# board.net
KiCad netlist of a schematic drawn in EAGLE
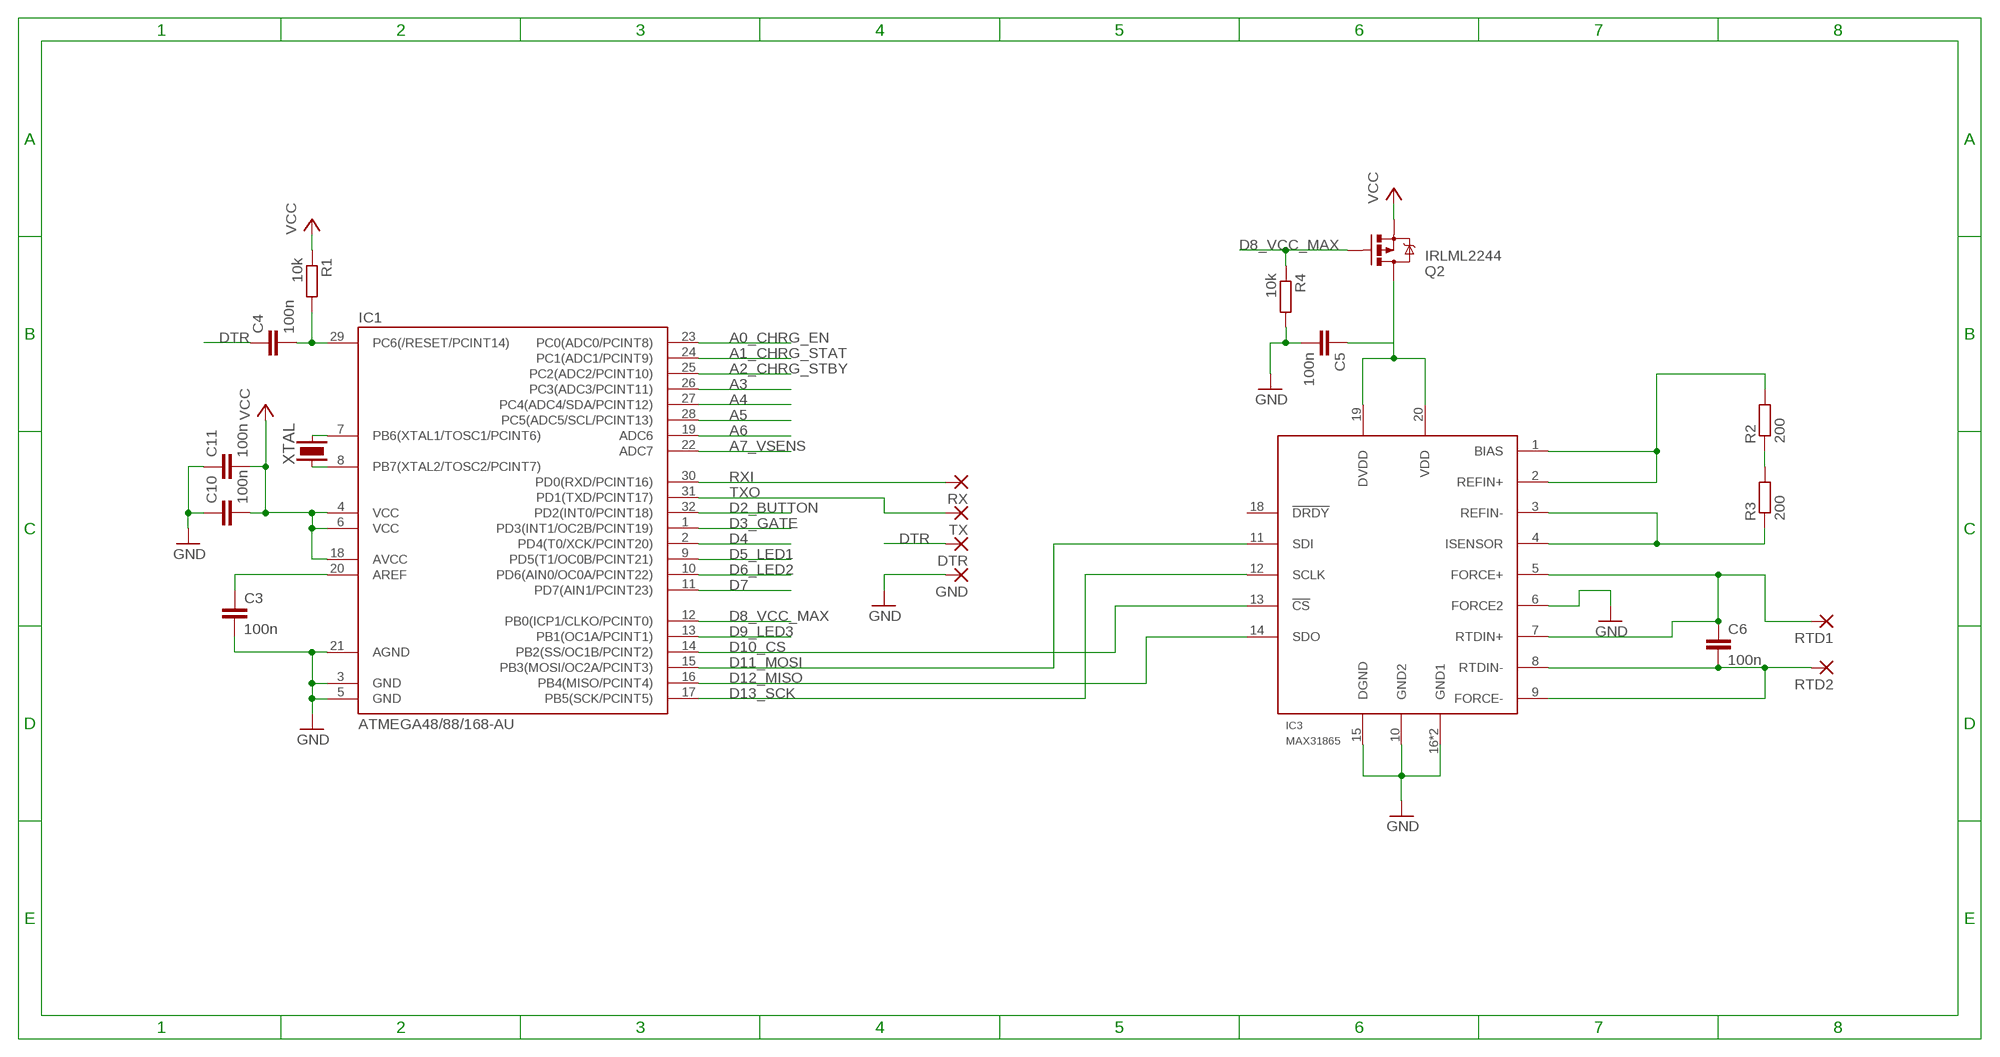
[diagram p0: schematic, sheet 1]
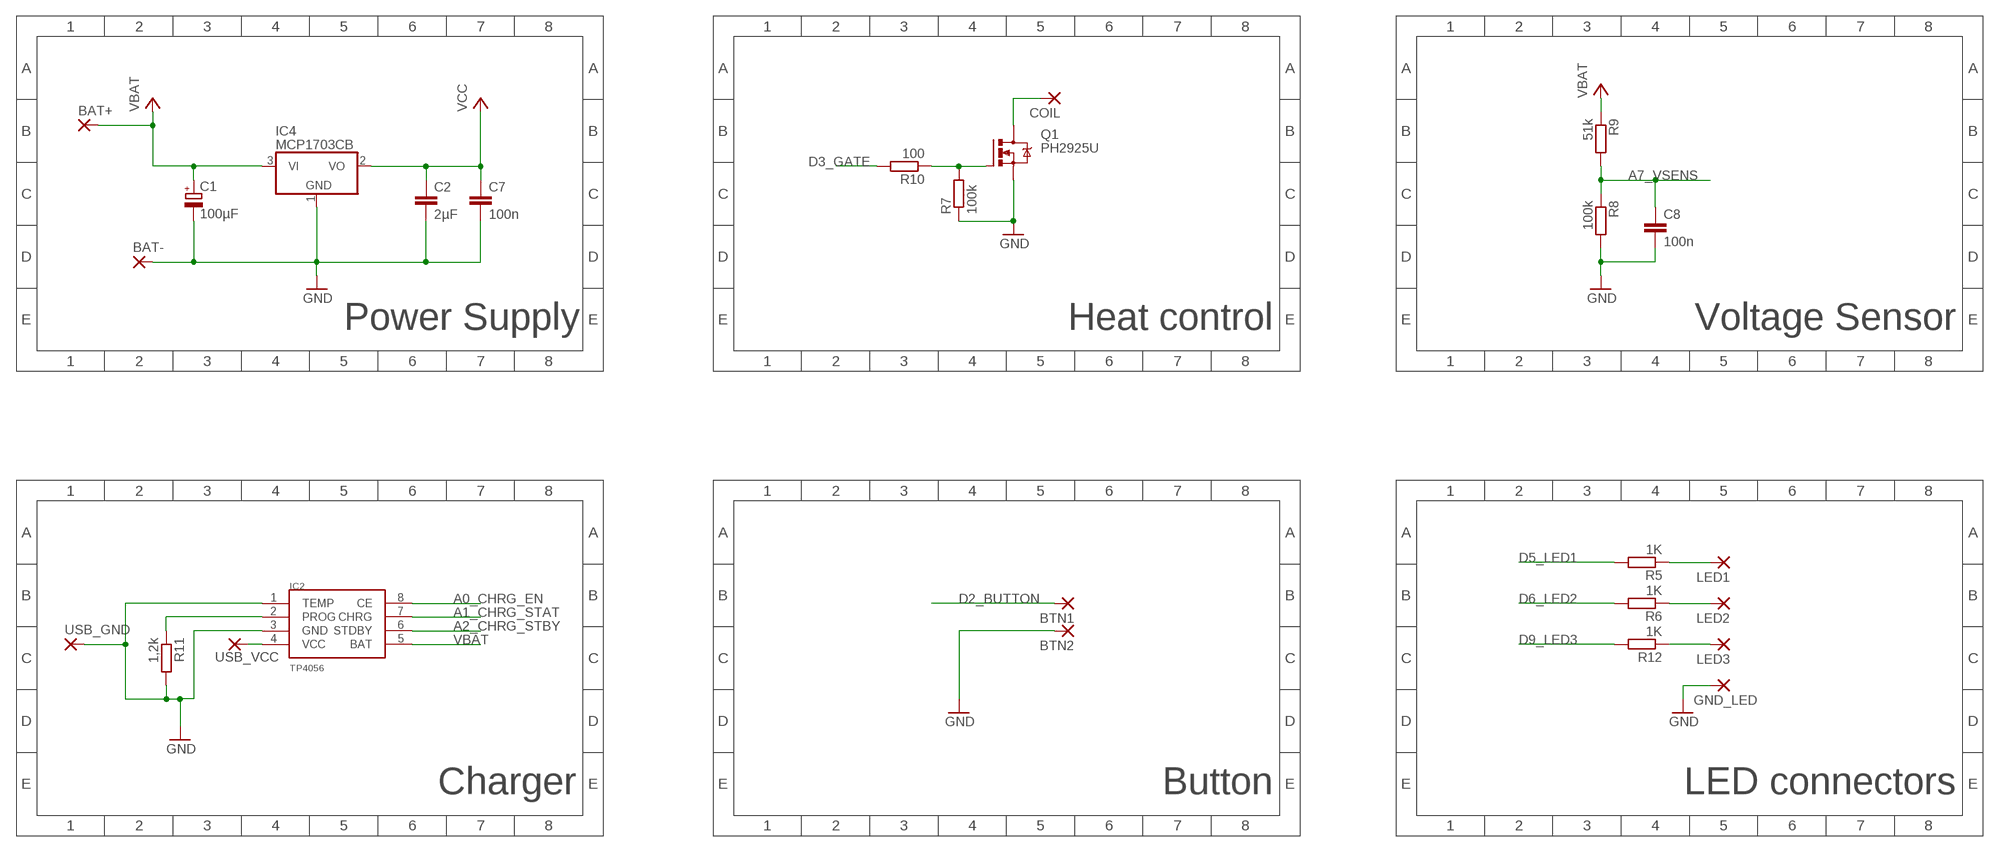
[diagram p1: schematic, sheet 2]

(export (version "E")
  (design (tool "Eeschema 10.0.6"))
  (components
    (comp (ref "BAT+")
      (value "SMD2")
      (footprint "eagle-import:SMD1,27-2,54")
      (libsource (lib "eagle-import") (part "SMD2"))
    )
    (comp (ref "BAT-")
      (value "WIREPAD4,16O1,6")
      (footprint "eagle-import:4,16O1,6")
      (libsource (lib "eagle-import") (part "WIREPAD4,16O1,6"))
    )
    (comp (ref "BTN1")
      (value "SMD2")
      (footprint "eagle-import:SMD1,27-2,54")
      (libsource (lib "eagle-import") (part "SMD2"))
    )
    (comp (ref "BTN2")
      (value "SMD2")
      (footprint "eagle-import:SMD1,27-2,54")
      (libsource (lib "eagle-import") (part "SMD2"))
    )
    (comp (ref "C1")
      (value "100µF")
      (footprint "eagle-import:CT7343")
      (libsource (lib "eagle-import") (part "CPOL-EUCT7343"))
    )
    (comp (ref "C2")
      (value "2µF")
      (footprint "eagle-import:C1206")
      (libsource (lib "eagle-import") (part "C-EUC1206"))
    )
    (comp (ref "C7")
      (value "100n")
      (footprint "eagle-import:C0603")
      (libsource (lib "eagle-import") (part "C-EUC0603"))
    )
    (comp (ref "C8")
      (value "100n")
      (footprint "eagle-import:C0603")
      (libsource (lib "eagle-import") (part "C-EUC0603"))
    )
    (comp (ref "COIL")
      (value "WIREPAD4,16O1,6")
      (footprint "eagle-import:4,16O1,6")
      (libsource (lib "eagle-import") (part "WIREPAD4,16O1,6"))
    )
    (comp (ref "GND_LED")
      (value "SMD2")
      (footprint "eagle-import:SMD1,27-2,54")
      (libsource (lib "eagle-import") (part "SMD2"))
    )
    (comp (ref "IC2")
      (value "TP4056")
      (footprint "eagle-import:SOP-8")
      (libsource (lib "eagle-import") (part "TP4056"))
    )
    (comp (ref "IC4")
      (value "MCP1703CB")
      (footprint "eagle-import:SOT23")
      (libsource (lib "eagle-import") (part "MCP1703CB"))
    )
    (comp (ref "LED1")
      (value "SMD2")
      (footprint "eagle-import:SMD1,27-2,54")
      (libsource (lib "eagle-import") (part "SMD2"))
    )
    (comp (ref "LED2")
      (value "SMD2")
      (footprint "eagle-import:SMD1,27-2,54")
      (libsource (lib "eagle-import") (part "SMD2"))
    )
    (comp (ref "LED3")
      (value "SMD2")
      (footprint "eagle-import:SMD1,27-2,54")
      (libsource (lib "eagle-import") (part "SMD2"))
    )
    (comp (ref "Q1")
      (value "PH2925U")
      (footprint "eagle-import:SOT-669")
      (libsource (lib "eagle-import") (part "PH2925U"))
    )
    (comp (ref "R5")
      (value "1K")
      (footprint "eagle-import:R0603")
      (libsource (lib "eagle-import") (part "R-EU_R0603"))
    )
    (comp (ref "R6")
      (value "1K")
      (footprint "eagle-import:R0603")
      (libsource (lib "eagle-import") (part "R-EU_R0603"))
    )
    (comp (ref "R7")
      (value "100k")
      (footprint "eagle-import:R0603")
      (libsource (lib "eagle-import") (part "R-EU_R0603"))
    )
    (comp (ref "R8")
      (value "100k")
      (footprint "eagle-import:R0603")
      (libsource (lib "eagle-import") (part "R-EU_R0603"))
    )
    (comp (ref "R9")
      (value "51k")
      (footprint "eagle-import:R0603")
      (libsource (lib "eagle-import") (part "R-EU_R0603"))
    )
    (comp (ref "R10")
      (value "100")
      (footprint "eagle-import:R0603")
      (libsource (lib "eagle-import") (part "R-EU_R0603"))
    )
    (comp (ref "R11")
      (value "1,2k")
      (footprint "eagle-import:R0603")
      (libsource (lib "eagle-import") (part "R-EU_R0603"))
    )
    (comp (ref "R12")
      (value "1K")
      (footprint "eagle-import:R0603")
      (libsource (lib "eagle-import") (part "R-EU_R0603"))
    )
    (comp (ref "USB_GND")
      (value "SMD2")
      (footprint "eagle-import:SMD1,27-2,54")
      (libsource (lib "eagle-import") (part "SMD2"))
    )
    (comp (ref "USB_VCC")
      (value "SMD2")
      (footprint "eagle-import:SMD1,27-2,54")
      (libsource (lib "eagle-import") (part "SMD2"))
    )
    (comp (ref "C3")
      (value "100n")
      (footprint "eagle-import:C0603")
      (libsource (lib "eagle-import") (part "C-EUC0603"))
    )
    (comp (ref "C4")
      (value "100n")
      (footprint "eagle-import:C0603")
      (libsource (lib "eagle-import") (part "C-EUC0603"))
    )
    (comp (ref "C5")
      (value "100n")
      (footprint "eagle-import:C0603")
      (libsource (lib "eagle-import") (part "C-EUC0603"))
    )
    (comp (ref "C6")
      (value "100n")
      (footprint "eagle-import:C0603")
      (libsource (lib "eagle-import") (part "C-EUC0603"))
    )
    (comp (ref "C10")
      (value "100n")
      (footprint "eagle-import:C0603")
      (libsource (lib "eagle-import") (part "C-EUC0603"))
    )
    (comp (ref "C11")
      (value "100n")
      (footprint "eagle-import:C0603")
      (libsource (lib "eagle-import") (part "C-EUC0603"))
    )
    (comp (ref "DTR")
      (value "SMD2")
      (footprint "eagle-import:SMD1,27-2,54")
      (libsource (lib "eagle-import") (part "SMD2"))
    )
    (comp (ref "GND")
      (value "SMD2")
      (footprint "eagle-import:SMD1,27-2,54")
      (libsource (lib "eagle-import") (part "SMD2"))
    )
    (comp (ref "IC1")
      (value "ATMEGA48/88/168-AU")
      (footprint "eagle-import:TQFP32-08")
      (libsource (lib "eagle-import") (part "ATMEGA48/88/168-AU"))
    )
    (comp (ref "IC3")
      (value "MAX31865")
      (footprint "eagle-import:TQFN20-5X5")
      (libsource (lib "eagle-import") (part "MAX31865"))
    )
    (comp (ref "Q2")
      (value "IRLML2244")
      (footprint "eagle-import:SOT23-3")
      (libsource (lib "eagle-import") (part "MOSFET-PCHANNELIRLML2244"))
    )
    (comp (ref "R1")
      (value "10k")
      (footprint "eagle-import:R0603")
      (libsource (lib "eagle-import") (part "R-EU_R0603"))
    )
    (comp (ref "R2")
      (value "200")
      (footprint "eagle-import:R0603")
      (libsource (lib "eagle-import") (part "R-EU_R0603"))
    )
    (comp (ref "R3")
      (value "200")
      (footprint "eagle-import:R0603")
      (libsource (lib "eagle-import") (part "R-EU_R0603"))
    )
    (comp (ref "R4")
      (value "10k")
      (footprint "eagle-import:R0603")
      (libsource (lib "eagle-import") (part "R-EU_R0603"))
    )
    (comp (ref "RTD1")
      (value "SMD2")
      (footprint "eagle-import:SMD1,27-2,54")
      (libsource (lib "eagle-import") (part "SMD2"))
    )
    (comp (ref "RTD2")
      (value "SMD2")
      (footprint "eagle-import:SMD1,27-2,54")
      (libsource (lib "eagle-import") (part "SMD2"))
    )
    (comp (ref "RX")
      (value "SMD2")
      (footprint "eagle-import:SMD1,27-2,54")
      (libsource (lib "eagle-import") (part "SMD2"))
    )
    (comp (ref "TX")
      (value "SMD2")
      (footprint "eagle-import:SMD1,27-2,54")
      (libsource (lib "eagle-import") (part "SMD2"))
    )
    (comp (ref "XTAL")
      (value "XTAL-HCS10")
      (footprint "eagle-import:CS10")
      (libsource (lib "eagle-import") (part "XTAL-HCS10"))
    )
  )
  (nets
    (net (code "1") (name "A0_CHRG_EN") (class "Default")
      (node (ref "IC1") (pin "23") (pinfunction "PC0(ADC0/PCINT8)_23") (pintype "bidirectional"))
      (node (ref "IC2") (pin "8") (pinfunction "CE_8") (pintype "bidirectional"))
    )
    (net (code "2") (name "A1_CHRG_STAT") (class "Default")
      (node (ref "IC1") (pin "24") (pinfunction "PC1(ADC1/PCINT9)_24") (pintype "bidirectional"))
      (node (ref "IC2") (pin "7") (pinfunction "CHRG_7") (pintype "bidirectional"))
    )
    (net (code "3") (name "A2_CHRG_STBY") (class "Default")
      (node (ref "IC1") (pin "25") (pinfunction "PC2(ADC2/PCINT10)_25") (pintype "bidirectional"))
      (node (ref "IC2") (pin "6") (pinfunction "STDBY_6") (pintype "bidirectional"))
    )
    (net (code "4") (name "A3") (class "Default")
      (node (ref "IC1") (pin "26") (pinfunction "PC3(ADC3/PCINT11)_26") (pintype "bidirectional"))
    )
    (net (code "5") (name "A4") (class "Default")
      (node (ref "IC1") (pin "27") (pinfunction "PC4(ADC4/SDA/PCINT12)_27") (pintype "bidirectional"))
    )
    (net (code "6") (name "A5") (class "Default")
      (node (ref "IC1") (pin "28") (pinfunction "PC5(ADC5/SCL/PCINT13)_28") (pintype "bidirectional"))
    )
    (net (code "7") (name "A6") (class "Default")
      (node (ref "IC1") (pin "19") (pinfunction "ADC6_19") (pintype "passive"))
    )
    (net (code "8") (name "A7_VSENS") (class "Default")
      (node (ref "C8") (pin "1") (pinfunction "1_1") (pintype "passive"))
      (node (ref "IC1") (pin "22") (pinfunction "ADC7_22") (pintype "passive"))
      (node (ref "R8") (pin "1") (pinfunction "1_1") (pintype "passive"))
      (node (ref "R9") (pin "2") (pinfunction "2_2") (pintype "passive"))
    )
    (net (code "9") (name "D2_BUTTON") (class "Default")
      (node (ref "BTN1") (pin "1") (pinfunction "P_1") (pintype "passive"))
      (node (ref "IC1") (pin "32") (pinfunction "PD2(INT0/PCINT18)_32") (pintype "bidirectional"))
    )
    (net (code "10") (name "D3_GATE") (class "Default")
      (node (ref "IC1") (pin "1") (pinfunction "PD3(INT1/OC2B/PCINT19)_1") (pintype "bidirectional"))
      (node (ref "R10") (pin "2") (pinfunction "2_2") (pintype "passive"))
    )
    (net (code "11") (name "D4") (class "Default")
      (node (ref "IC1") (pin "2") (pinfunction "PD4(T0/XCK/PCINT20)_2") (pintype "bidirectional"))
    )
    (net (code "12") (name "D5_LED1") (class "Default")
      (node (ref "IC1") (pin "9") (pinfunction "PD5(T1/OC0B/PCINT21)_9") (pintype "bidirectional"))
      (node (ref "R5") (pin "2") (pinfunction "2_2") (pintype "passive"))
    )
    (net (code "13") (name "D6_LED2") (class "Default")
      (node (ref "IC1") (pin "10") (pinfunction "PD6(AIN0/OC0A/PCINT22)_10") (pintype "bidirectional"))
      (node (ref "R6") (pin "2") (pinfunction "2_2") (pintype "passive"))
    )
    (net (code "14") (name "D7") (class "Default")
      (node (ref "IC1") (pin "11") (pinfunction "PD7(AIN1/PCINT23)_11") (pintype "bidirectional"))
    )
    (net (code "15") (name "D8_VCC_MAX") (class "Default")
      (node (ref "IC1") (pin "12") (pinfunction "PB0(ICP1/CLKO/PCINT0)_12") (pintype "bidirectional"))
      (node (ref "Q2") (pin "1") (pinfunction "G_1") (pintype "passive"))
      (node (ref "R4") (pin "1") (pinfunction "1_1") (pintype "passive"))
    )
    (net (code "16") (name "D9_LED3") (class "Default")
      (node (ref "IC1") (pin "13") (pinfunction "PB1(OC1A/PCINT1)_13") (pintype "bidirectional"))
      (node (ref "R12") (pin "2") (pinfunction "2_2") (pintype "passive"))
    )
    (net (code "17") (name "D10_CS") (class "Default")
      (node (ref "IC1") (pin "14") (pinfunction "PB2(SS/OC1B/PCINT2)_14") (pintype "bidirectional"))
      (node (ref "IC3") (pin "13") (pinfunction "~{CS}_13") (pintype "input"))
    )
    (net (code "18") (name "D11_MOSI") (class "Default")
      (node (ref "IC1") (pin "15") (pinfunction "PB3(MOSI/OC2A/PCINT3)_15") (pintype "bidirectional"))
      (node (ref "IC3") (pin "11") (pinfunction "SDI_11") (pintype "input"))
    )
    (net (code "19") (name "D12_MISO") (class "Default")
      (node (ref "IC1") (pin "16") (pinfunction "PB4(MISO/PCINT4)_16") (pintype "bidirectional"))
      (node (ref "IC3") (pin "14") (pinfunction "SDO_14") (pintype "output"))
    )
    (net (code "20") (name "D13_SCK") (class "Default")
      (node (ref "IC1") (pin "17") (pinfunction "PB5(SCK/PCINT5)_17") (pintype "bidirectional"))
      (node (ref "IC3") (pin "12") (pinfunction "SCLK_12") (pintype "input"))
    )
    (net (code "21") (name "DTR") (class "Default")
      (node (ref "C4") (pin "1") (pinfunction "1_1") (pintype "passive"))
      (node (ref "DTR") (pin "1") (pinfunction "P_1") (pintype "passive"))
    )
    (net (code "22") (name "GND") (class "Default")
      (node (ref "BAT-") (pin "1") (pinfunction "P_1") (pintype "passive"))
      (node (ref "BTN2") (pin "1") (pinfunction "P_1") (pintype "passive"))
      (node (ref "C1") (pin "-") (pinfunction "-_-") (pintype "passive"))
      (node (ref "C10") (pin "1") (pinfunction "1_1") (pintype "passive"))
      (node (ref "C11") (pin "1") (pinfunction "1_1") (pintype "passive"))
      (node (ref "C2") (pin "2") (pinfunction "2_2") (pintype "passive"))
      (node (ref "C3") (pin "2") (pinfunction "2_2") (pintype "passive"))
      (node (ref "C5") (pin "2") (pinfunction "2_2") (pintype "passive"))
      (node (ref "C7") (pin "2") (pinfunction "2_2") (pintype "passive"))
      (node (ref "C8") (pin "2") (pinfunction "2_2") (pintype "passive"))
      (node (ref "GND") (pin "1") (pinfunction "P_1") (pintype "passive"))
      (node (ref "GND_LED") (pin "1") (pinfunction "P_1") (pintype "passive"))
      (node (ref "IC1") (pin "21") (pinfunction "AGND_21") (pintype "power_in"))
      (node (ref "IC1") (pin "3") (pinfunction "GND_3") (pintype "power_in"))
      (node (ref "IC1") (pin "5") (pinfunction "GND_5") (pintype "power_in"))
      (node (ref "IC2") (pin "1") (pinfunction "TEMP_1") (pintype "bidirectional"))
      (node (ref "IC2") (pin "3") (pinfunction "GND_3") (pintype "bidirectional"))
      (node (ref "IC3") (pin "10") (pinfunction "GND2_10") (pintype "power_in"))
      (node (ref "IC3") (pin "15") (pinfunction "DGND_15") (pintype "power_in"))
      (node (ref "IC3") (pin "16") (pinfunction "GND1_16") (pintype "power_in"))
      (node (ref "IC3") (pin "6") (pinfunction "FORCE2_6") (pintype "input"))
      (node (ref "IC3") (pin "EXP") (pinfunction "GND1_EXP") (pintype "power_in"))
      (node (ref "IC4") (pin "1") (pinfunction "GND_1") (pintype "passive"))
      (node (ref "Q1") (pin "1") (pinfunction "S_1") (pintype "passive"))
      (node (ref "Q1") (pin "2") (pinfunction "S_2") (pintype "passive"))
      (node (ref "Q1") (pin "3") (pinfunction "S_3") (pintype "passive"))
      (node (ref "R11") (pin "2") (pinfunction "2_2") (pintype "passive"))
      (node (ref "R4") (pin "2") (pinfunction "2_2") (pintype "passive"))
      (node (ref "R7") (pin "1") (pinfunction "1_1") (pintype "passive"))
      (node (ref "R8") (pin "2") (pinfunction "2_2") (pintype "passive"))
      (node (ref "USB_GND") (pin "1") (pinfunction "P_1") (pintype "passive"))
    )
    (net (code "23") (name "Net-(COIL-P)") (class "Default")
      (node (ref "COIL") (pin "1") (pinfunction "P_1") (pintype "passive"))
      (node (ref "Q1") (pin "5") (pinfunction "D_5") (pintype "passive"))
    )
    (net (code "24") (name "Net-(IC1-AREF)") (class "Default")
      (node (ref "C3") (pin "1") (pinfunction "1_1") (pintype "passive"))
      (node (ref "IC1") (pin "20") (pinfunction "AREF_20") (pintype "passive"))
    )
    (net (code "25") (name "Net-(IC1-PB6(XTAL1{slash}TOSC1{slash}PCINT6))") (class "Default")
      (node (ref "IC1") (pin "7") (pinfunction "PB6(XTAL1/TOSC1/PCINT6)_7") (pintype "bidirectional"))
      (node (ref "XTAL") (pin "R") (pinfunction "P2_R") (pintype "passive"))
    )
    (net (code "26") (name "Net-(IC1-PB7(XTAL2{slash}TOSC2{slash}PCINT7))") (class "Default")
      (node (ref "IC1") (pin "8") (pinfunction "PB7(XTAL2/TOSC2/PCINT7)_8") (pintype "bidirectional"))
      (node (ref "XTAL") (pin "L") (pinfunction "P1_L") (pintype "passive"))
    )
    (net (code "27") (name "Net-(IC1-PC6({slash}RESET{slash}PCINT14))") (class "Default")
      (node (ref "C4") (pin "2") (pinfunction "2_2") (pintype "passive"))
      (node (ref "IC1") (pin "29") (pinfunction "PC6(/RESET/PCINT14)_29") (pintype "bidirectional"))
      (node (ref "R1") (pin "2") (pinfunction "2_2") (pintype "passive"))
    )
    (net (code "28") (name "Net-(IC2-PROG)") (class "Default")
      (node (ref "IC2") (pin "2") (pinfunction "PROG_2") (pintype "bidirectional"))
      (node (ref "R11") (pin "1") (pinfunction "1_1") (pintype "passive"))
    )
    (net (code "29") (name "Net-(IC2-VCC)") (class "Default")
      (node (ref "IC2") (pin "4") (pinfunction "VCC_4") (pintype "bidirectional"))
      (node (ref "USB_VCC") (pin "1") (pinfunction "P_1") (pintype "passive"))
    )
    (net (code "30") (name "Net-(IC3-BIAS)") (class "Default")
      (node (ref "IC3") (pin "1") (pinfunction "BIAS_1") (pintype "input"))
      (node (ref "IC3") (pin "2") (pinfunction "REFIN+_2") (pintype "input"))
      (node (ref "R2") (pin "2") (pinfunction "2_2") (pintype "passive"))
    )
    (net (code "31") (name "Net-(IC3-DVDD)") (class "Default")
      (node (ref "C5") (pin "1") (pinfunction "1_1") (pintype "passive"))
      (node (ref "IC3") (pin "19") (pinfunction "DVDD_19") (pintype "power_in"))
      (node (ref "IC3") (pin "20") (pinfunction "VDD_20") (pintype "power_in"))
      (node (ref "Q2") (pin "3") (pinfunction "D_3") (pintype "passive"))
    )
    (net (code "32") (name "Net-(IC3-FORCE+)") (class "Default")
      (node (ref "C6") (pin "1") (pinfunction "1_1") (pintype "passive"))
      (node (ref "IC3") (pin "5") (pinfunction "FORCE+_5") (pintype "input"))
      (node (ref "IC3") (pin "7") (pinfunction "RTDIN+_7") (pintype "input"))
      (node (ref "RTD1") (pin "1") (pinfunction "P_1") (pintype "passive"))
    )
    (net (code "33") (name "Net-(IC3-FORCE-)") (class "Default")
      (node (ref "C6") (pin "2") (pinfunction "2_2") (pintype "passive"))
      (node (ref "IC3") (pin "8") (pinfunction "RTDIN-_8") (pintype "input"))
      (node (ref "IC3") (pin "9") (pinfunction "FORCE-_9") (pintype "input"))
      (node (ref "RTD2") (pin "1") (pinfunction "P_1") (pintype "passive"))
    )
    (net (code "34") (name "Net-(IC3-ISENSOR)") (class "Default")
      (node (ref "IC3") (pin "3") (pinfunction "REFIN-_3") (pintype "input"))
      (node (ref "IC3") (pin "4") (pinfunction "ISENSOR_4") (pintype "input"))
      (node (ref "R3") (pin "1") (pinfunction "1_1") (pintype "passive"))
    )
    (net (code "35") (name "Net-(LED1-P)") (class "Default")
      (node (ref "LED1") (pin "1") (pinfunction "P_1") (pintype "passive"))
      (node (ref "R5") (pin "1") (pinfunction "1_1") (pintype "passive"))
    )
    (net (code "36") (name "Net-(LED2-P)") (class "Default")
      (node (ref "LED2") (pin "1") (pinfunction "P_1") (pintype "passive"))
      (node (ref "R6") (pin "1") (pinfunction "1_1") (pintype "passive"))
    )
    (net (code "37") (name "Net-(LED3-P)") (class "Default")
      (node (ref "LED3") (pin "1") (pinfunction "P_1") (pintype "passive"))
      (node (ref "R12") (pin "1") (pinfunction "1_1") (pintype "passive"))
    )
    (net (code "38") (name "Net-(Q1-G)") (class "Default")
      (node (ref "Q1") (pin "4") (pinfunction "G_4") (pintype "passive"))
      (node (ref "R10") (pin "1") (pinfunction "1_1") (pintype "passive"))
      (node (ref "R7") (pin "2") (pinfunction "2_2") (pintype "passive"))
    )
    (net (code "39") (name "Net-(R2-Pad1)") (class "Default")
      (node (ref "R2") (pin "1") (pinfunction "1_1") (pintype "passive"))
      (node (ref "R3") (pin "2") (pinfunction "2_2") (pintype "passive"))
    )
    (net (code "40") (name "RXI") (class "Default")
      (node (ref "IC1") (pin "30") (pinfunction "PD0(RXD/PCINT16)_30") (pintype "bidirectional"))
      (node (ref "RX") (pin "1") (pinfunction "P_1") (pintype "passive"))
    )
    (net (code "41") (name "TXO") (class "Default")
      (node (ref "IC1") (pin "31") (pinfunction "PD1(TXD/PCINT17)_31") (pintype "bidirectional"))
      (node (ref "TX") (pin "1") (pinfunction "P_1") (pintype "passive"))
    )
    (net (code "42") (name "VBAT") (class "Default")
      (node (ref "BAT+") (pin "1") (pinfunction "P_1") (pintype "passive"))
      (node (ref "C1") (pin "+") (pinfunction "+_+") (pintype "passive"))
      (node (ref "IC2") (pin "5") (pinfunction "BAT_5") (pintype "bidirectional"))
      (node (ref "IC4") (pin "3") (pinfunction "VI_3") (pintype "input"))
      (node (ref "R9") (pin "1") (pinfunction "1_1") (pintype "passive"))
    )
    (net (code "43") (name "VCC") (class "Default")
      (node (ref "C10") (pin "2") (pinfunction "2_2") (pintype "passive"))
      (node (ref "C11") (pin "2") (pinfunction "2_2") (pintype "passive"))
      (node (ref "C2") (pin "1") (pinfunction "1_1") (pintype "passive"))
      (node (ref "C7") (pin "1") (pinfunction "1_1") (pintype "passive"))
      (node (ref "IC1") (pin "18") (pinfunction "AVCC_18") (pintype "passive"))
      (node (ref "IC1") (pin "4") (pinfunction "VCC_4") (pintype "power_in"))
      (node (ref "IC1") (pin "6") (pinfunction "VCC_6") (pintype "power_in"))
      (node (ref "IC4") (pin "2") (pinfunction "VO_2") (pintype "passive"))
      (node (ref "Q2") (pin "2") (pinfunction "S_2") (pintype "passive"))
      (node (ref "R1") (pin "1") (pinfunction "1_1") (pintype "passive"))
    )
    (net (code "44") (name "unconnected-(IC3-~{DRDY}-Pad18)") (class "Default")
      (node (ref "IC3") (pin "18") (pinfunction "~{DRDY}_18") (pintype "output"))
    )
  )
)
